# OVP_OCP.net
KiCad netlist of a schematic drawn in Altium Designer
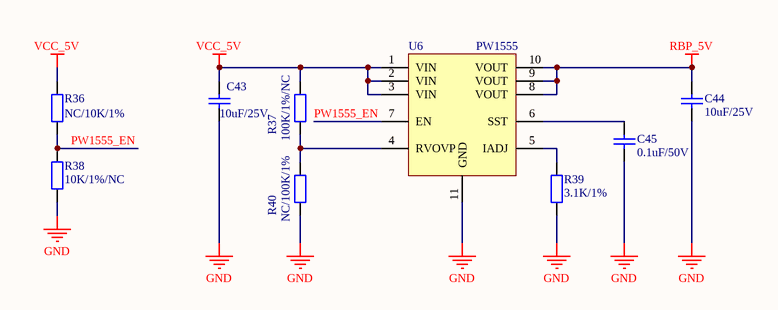
[diagram p0: OVP_OCP.SchDoc]

(export (version "E")
  (design (tool "Eeschema 10.0.6"))
  (components
    (comp (ref "C43")
      (value "10uF/25V")
      (footprint "C0805_L")
      (description "贴片电容")
      (libsource (lib "0.1 - 电阻-电容-电感-晶振-晶体-磁珠-电位器") (part "C"))
    )
    (comp (ref "C44")
      (value "10uF/25V")
      (footprint "C0805_L")
      (description "贴片电容")
      (libsource (lib "0.1 - 电阻-电容-电感-晶振-晶体-磁珠-电位器") (part "C"))
    )
    (comp (ref "C45")
      (value "0.1uF/50V")
      (footprint "C0402_L")
      (description "贴片电容")
      (libsource (lib "0.1 - 电阻-电容-电感-晶振-晶体-磁珠-电位器") (part "C"))
    )
    (comp (ref "R36")
      (value "NC/10K/1%")
      (footprint "R0402_L")
      (description "贴片电阻")
      (libsource (lib "0.1 - 电阻-电容-电感-晶振-晶体-磁珠-电位器") (part "R"))
    )
    (comp (ref "R37")
      (value "100K/1%/NC")
      (footprint "R0402_L")
      (description "贴片电阻")
      (libsource (lib "0.1 - 电阻-电容-电感-晶振-晶体-磁珠-电位器") (part "R"))
    )
    (comp (ref "R38")
      (value "10K/1%/NC")
      (footprint "R0402_L")
      (description "贴片电阻")
      (libsource (lib "0.1 - 电阻-电容-电感-晶振-晶体-磁珠-电位器") (part "R"))
    )
    (comp (ref "R39")
      (value "3.1K/1%")
      (footprint "R0402_L")
      (description "贴片电阻")
      (libsource (lib "0.1 - 电阻-电容-电感-晶振-晶体-磁珠-电位器") (part "R"))
    )
    (comp (ref "R40")
      (value "NC/100K/1%")
      (footprint "R0402_L")
      (description "贴片电阻")
      (libsource (lib "0.1 - 电阻-电容-电感-晶振-晶体-磁珠-电位器") (part "R"))
    )
    (comp (ref "U6")
      (value "PW1555")
      (footprint "DFN3x3-10")
      (description "VOVP  ILIM保护芯片")
      (libsource (lib "USER_Lib") (part "PW1555"))
    )
  )
  (nets
    (net (code "1") (name "/PW1555_EN") (class "Default")
      (node (ref "R36") (pin "1") (pinfunction "1_1") (pintype "passive"))
      (node (ref "R38") (pin "2") (pinfunction "2_2") (pintype "passive"))
      (node (ref "U6") (pin "7") (pinfunction "EN_7") (pintype "passive"))
    )
    (net (code "2") (name "GND") (class "Default")
      (node (ref "C43") (pin "1") (pinfunction "1_1") (pintype "passive"))
      (node (ref "C44") (pin "1") (pinfunction "1_1") (pintype "passive"))
      (node (ref "C45") (pin "1") (pinfunction "1_1") (pintype "passive"))
      (node (ref "R38") (pin "1") (pinfunction "1_1") (pintype "passive"))
      (node (ref "R39") (pin "1") (pinfunction "1_1") (pintype "passive"))
      (node (ref "R40") (pin "1") (pinfunction "1_1") (pintype "passive"))
      (node (ref "U6") (pin "11") (pinfunction "GND_11") (pintype "passive"))
    )
    (net (code "3") (name "Net-(U6-IADJ)") (class "Default")
      (node (ref "R39") (pin "2") (pinfunction "2_2") (pintype "passive"))
      (node (ref "U6") (pin "5") (pinfunction "IADJ_5") (pintype "passive"))
    )
    (net (code "4") (name "Net-(U6-RVOVP)") (class "Default")
      (node (ref "R37") (pin "1") (pinfunction "1_1") (pintype "passive"))
      (node (ref "R40") (pin "2") (pinfunction "2_2") (pintype "passive"))
      (node (ref "U6") (pin "4") (pinfunction "RVOVP_4") (pintype "passive"))
    )
    (net (code "5") (name "Net-(U6-SST)") (class "Default")
      (node (ref "C45") (pin "2") (pinfunction "2_2") (pintype "passive"))
      (node (ref "U6") (pin "6") (pinfunction "SST_6") (pintype "passive"))
    )
    (net (code "6") (name "RBP_5V") (class "Default")
      (node (ref "C44") (pin "2") (pinfunction "2_2") (pintype "passive"))
      (node (ref "U6") (pin "10") (pinfunction "VOUT_10") (pintype "passive"))
      (node (ref "U6") (pin "8") (pinfunction "VOUT_8") (pintype "passive"))
      (node (ref "U6") (pin "9") (pinfunction "VOUT_9") (pintype "passive"))
    )
    (net (code "7") (name "VCC_5V") (class "Default")
      (node (ref "C43") (pin "2") (pinfunction "2_2") (pintype "passive"))
      (node (ref "R36") (pin "2") (pinfunction "2_2") (pintype "passive"))
      (node (ref "R37") (pin "2") (pinfunction "2_2") (pintype "passive"))
      (node (ref "U6") (pin "1") (pinfunction "VIN_1") (pintype "passive"))
      (node (ref "U6") (pin "2") (pinfunction "VIN_2") (pintype "passive"))
      (node (ref "U6") (pin "3") (pinfunction "VIN_3") (pintype "passive"))
    )
  )
)
